# MCU_board_ATmega328p_v2_4_AW.net
KiCad netlist of a schematic drawn in EAGLE
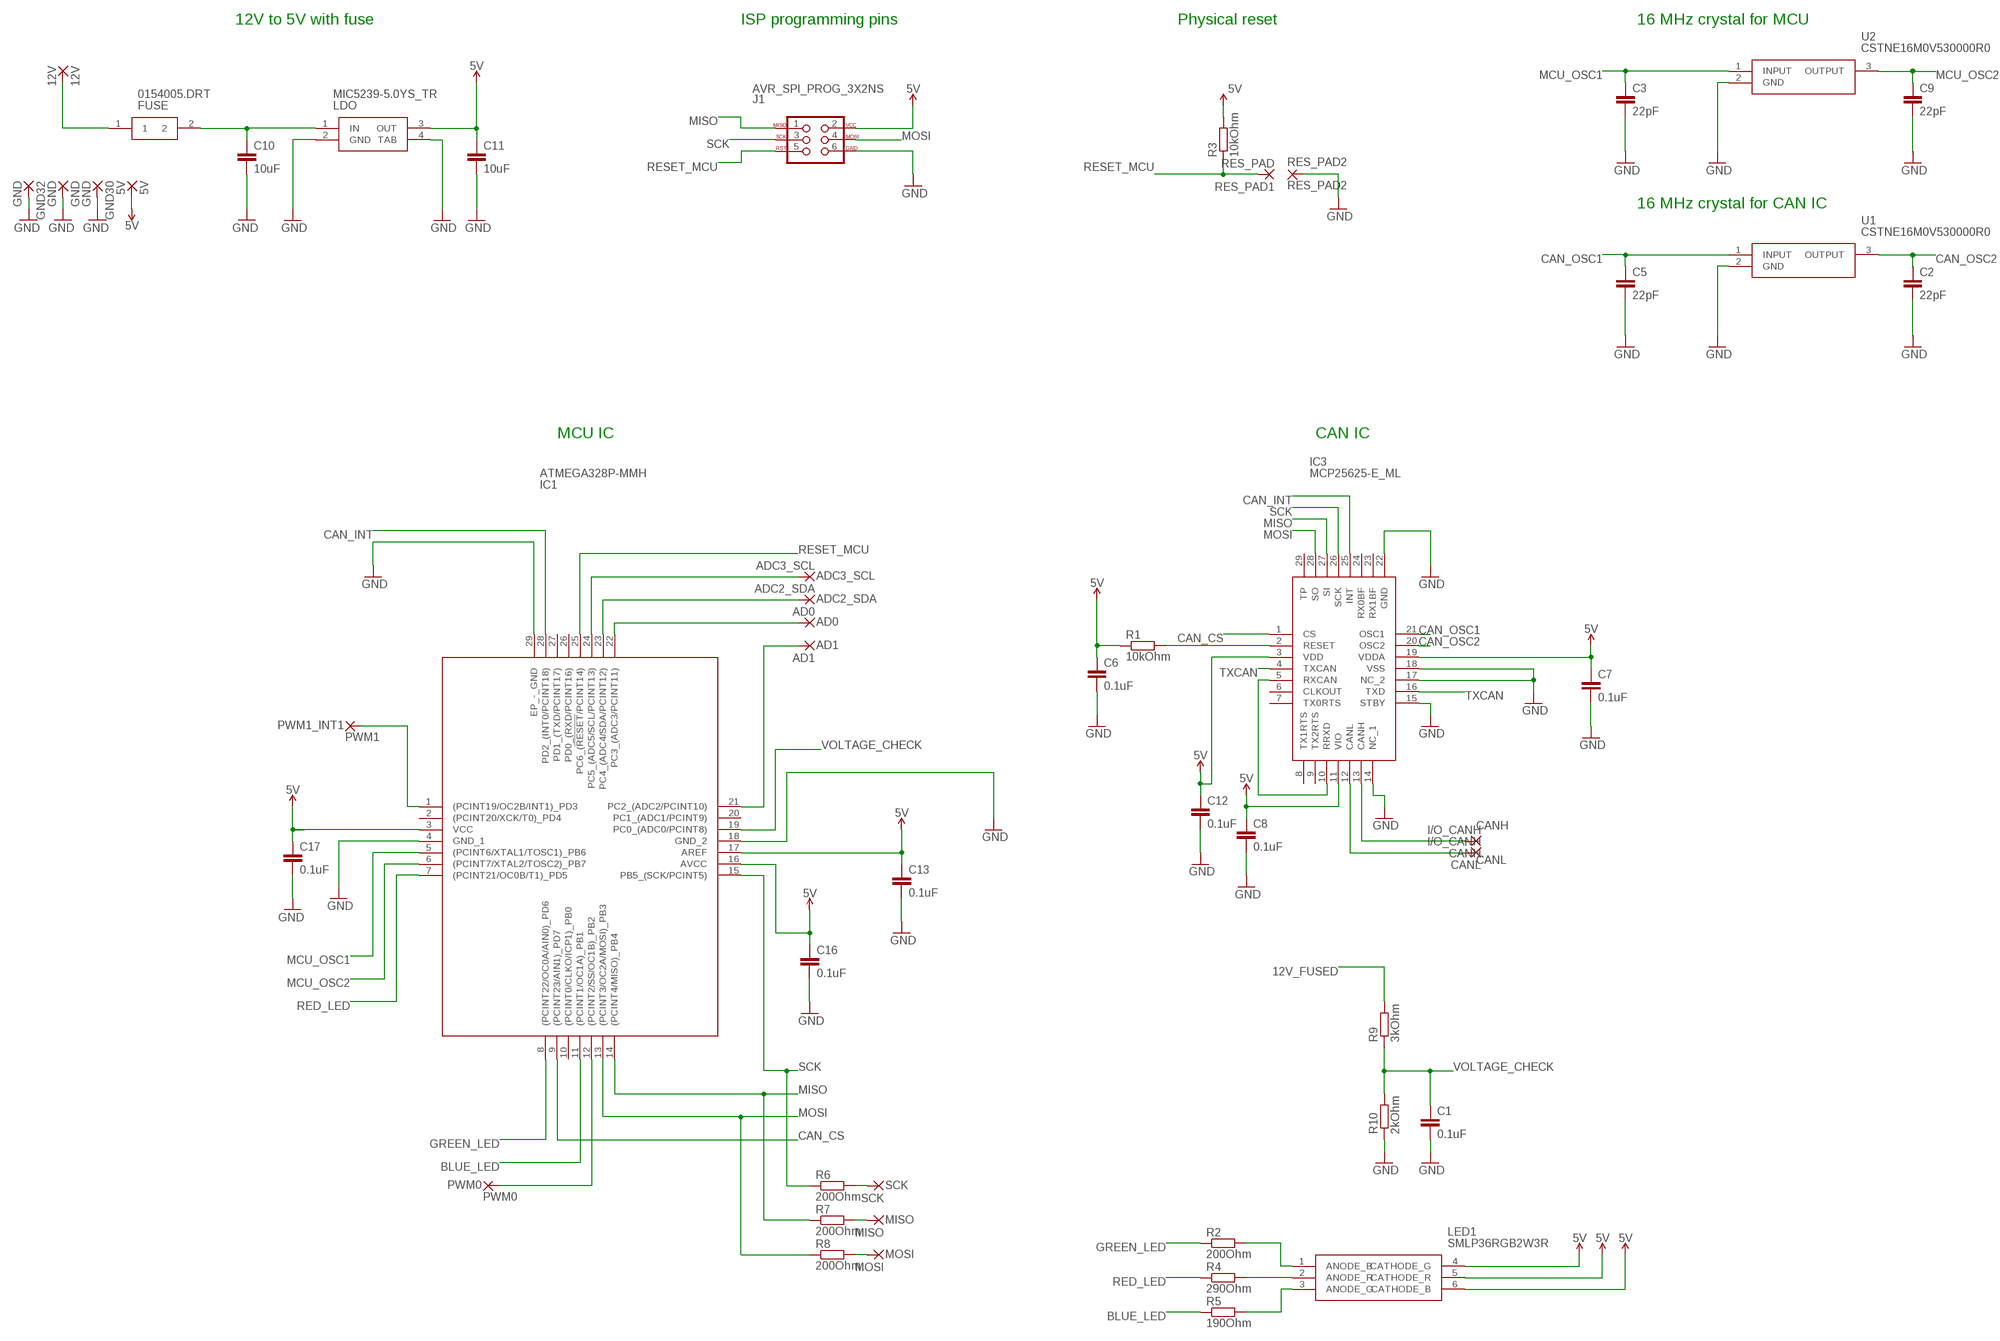
[diagram p0: schematic, sheet 1]

(export (version "E")
  (design (tool "Eeschema 10.0.6"))
  (components
    (comp (ref "5V")
      (value "5V")
      (footprint "eagle-import:2,15_1,0")
      (libsource (lib "eagle-import") (part "2,15/1,0"))
    )
    (comp (ref "12V")
      (value "12V")
      (footprint "eagle-import:2,15_1,0")
      (libsource (lib "eagle-import") (part "2,15/1,0"))
    )
    (comp (ref "AD0")
      (value "AD0")
      (footprint "eagle-import:2,15_1,0")
      (libsource (lib "eagle-import") (part "2,15/1,0"))
    )
    (comp (ref "AD1")
      (value "AD1")
      (footprint "eagle-import:2,15_1,0")
      (libsource (lib "eagle-import") (part "2,15/1,0"))
    )
    (comp (ref "ADC2_SDA")
      (value "ADC2_SDA")
      (footprint "eagle-import:2,15_1,0")
      (libsource (lib "eagle-import") (part "2,15/1,0"))
    )
    (comp (ref "ADC3_SCL")
      (value "ADC3_SCL")
      (footprint "eagle-import:2,15_1,0")
      (libsource (lib "eagle-import") (part "2,15/1,0"))
    )
    (comp (ref "C1")
      (value "0.1uF")
      (footprint "eagle-import:C0603")
      (libsource (lib "eagle-import") (part "CC0603"))
    )
    (comp (ref "C2")
      (value "22pF")
      (footprint "eagle-import:C0603")
      (libsource (lib "eagle-import") (part "CC0603"))
    )
    (comp (ref "C3")
      (value "22pF")
      (footprint "eagle-import:C0603")
      (libsource (lib "eagle-import") (part "CC0603"))
    )
    (comp (ref "C5")
      (value "22pF")
      (footprint "eagle-import:C0603")
      (libsource (lib "eagle-import") (part "CC0603"))
    )
    (comp (ref "C6")
      (value "0.1uF")
      (footprint "eagle-import:C0603")
      (libsource (lib "eagle-import") (part "CC0603"))
    )
    (comp (ref "C7")
      (value "0.1uF")
      (footprint "eagle-import:C0603")
      (libsource (lib "eagle-import") (part "CC0603"))
    )
    (comp (ref "C8")
      (value "0.1uF")
      (footprint "eagle-import:C0603")
      (libsource (lib "eagle-import") (part "CC0603"))
    )
    (comp (ref "C9")
      (value "22pF")
      (footprint "eagle-import:C0603")
      (libsource (lib "eagle-import") (part "CC0603"))
    )
    (comp (ref "C10")
      (value "10uF")
      (footprint "eagle-import:C0603")
      (libsource (lib "eagle-import") (part "CC0603"))
    )
    (comp (ref "C11")
      (value "10uF")
      (footprint "eagle-import:C0603")
      (libsource (lib "eagle-import") (part "CC0603"))
    )
    (comp (ref "C12")
      (value "0.1uF")
      (footprint "eagle-import:C0603")
      (libsource (lib "eagle-import") (part "CC0603"))
    )
    (comp (ref "C13")
      (value "0.1uF")
      (footprint "eagle-import:C0603")
      (libsource (lib "eagle-import") (part "CC0603"))
    )
    (comp (ref "C16")
      (value "0.1uF")
      (footprint "eagle-import:C0603")
      (libsource (lib "eagle-import") (part "CC0603"))
    )
    (comp (ref "C17")
      (value "0.1uF")
      (footprint "eagle-import:C0603")
      (libsource (lib "eagle-import") (part "CC0603"))
    )
    (comp (ref "CANH")
      (value "I/O_CANH")
      (footprint "eagle-import:2,15_1,0")
      (libsource (lib "eagle-import") (part "2,15/1,0"))
    )
    (comp (ref "CANL")
      (value "I/O_CANH")
      (footprint "eagle-import:2,15_1,0")
      (libsource (lib "eagle-import") (part "2,15/1,0"))
    )
    (comp (ref "FUSE")
      (value "0154005.DRT")
      (footprint "eagle-import:0154001.DRT")
      (fields (field (name "RS_PART_NUMBER") "2196260P"))
      (libsource (lib "eagle-import") (part "0154005.DRT"))
    )
    (comp (ref "GND")
      (value "GND")
      (footprint "eagle-import:2,15_1,0")
      (libsource (lib "eagle-import") (part "2,15/1,0"))
    )
    (comp (ref "GND30")
      (value "GND")
      (footprint "eagle-import:2,15_1,0")
      (libsource (lib "eagle-import") (part "2,15/1,0"))
    )
    (comp (ref "GND32")
      (value "GND")
      (footprint "eagle-import:2,15_1,0")
      (libsource (lib "eagle-import") (part "2,15/1,0"))
    )
    (comp (ref "IC1")
      (value "ATMEGA328P-MMH")
      (footprint "eagle-import:QFN45P400X400X100-29N")
      (fields (field (name "RS_PART_NUMBER") "1310272P"))
      (libsource (lib "eagle-import") (part "ATMEGA328P-MMH"))
    )
    (comp (ref "IC3")
      (value "MCP25625-E_ML")
      (footprint "eagle-import:QFN65P600X600X100-29N")
      (fields (field (name "ARROW_PART_NUMBER") "MCP25625-E/ML") (field (name "RS_PART_NUMBER") "1654104"))
      (libsource (lib "eagle-import") (part "MCP25625-E_ML"))
    )
    (comp (ref "J1")
      (value "AVR_SPI_PROG_3X2NS")
      (footprint "eagle-import:2X3-NS")
      (libsource (lib "eagle-import") (part "AVR_SPI_PROG_3X2NS"))
    )
    (comp (ref "LDO")
      (value "MIC5239-5.0YS_TR")
      (footprint "eagle-import:SOT230P700X170-4N")
      (fields
        (field (name "ARROW_PART_NUMBER") "MIC5239-5.0YS TR")
        (field (name "RS_PART_NUMBER") "7275535P")
      )
      (libsource (lib "eagle-import") (part "MIC5239-5.0YS_TR"))
    )
    (comp (ref "LED1")
      (value "SMLP36RGB2W3R")
      (footprint "eagle-import:ROHM-1510-(0604)")
      (fields (field (name "RS_PART_NUMBER") "1246884P"))
      (libsource (lib "eagle-import") (part "SMLP36RGB2W3R"))
    )
    (comp (ref "MISO")
      (value "MISO")
      (footprint "eagle-import:2,15_1,0")
      (libsource (lib "eagle-import") (part "2,15/1,0"))
    )
    (comp (ref "MOSI")
      (value "MOSI")
      (footprint "eagle-import:2,15_1,0")
      (libsource (lib "eagle-import") (part "2,15/1,0"))
    )
    (comp (ref "PWM0")
      (value "PWM0")
      (footprint "eagle-import:2,15_1,0")
      (libsource (lib "eagle-import") (part "2,15/1,0"))
    )
    (comp (ref "PWM1_INT1")
      (value "PWM1")
      (footprint "eagle-import:2,15_1,0")
      (libsource (lib "eagle-import") (part "2,15/1,0"))
    )
    (comp (ref "R1")
      (value "10kOhm")
      (footprint "eagle-import:R0603")
      (libsource (lib "eagle-import") (part "RR0603"))
    )
    (comp (ref "R2")
      (value "200Ohm")
      (footprint "eagle-import:R0603")
      (libsource (lib "eagle-import") (part "RR0603"))
    )
    (comp (ref "R3")
      (value "10kOhm")
      (footprint "eagle-import:R0603")
      (libsource (lib "eagle-import") (part "RR0603"))
    )
    (comp (ref "R4")
      (value "290Ohm")
      (footprint "eagle-import:R0603")
      (libsource (lib "eagle-import") (part "RR0603"))
    )
    (comp (ref "R5")
      (value "190Ohm")
      (footprint "eagle-import:R0603")
      (libsource (lib "eagle-import") (part "RR0603"))
    )
    (comp (ref "R6")
      (value "200Ohm")
      (footprint "eagle-import:R0603")
      (libsource (lib "eagle-import") (part "RR0603"))
    )
    (comp (ref "R7")
      (value "200Ohm")
      (footprint "eagle-import:R0603")
      (libsource (lib "eagle-import") (part "RR0603"))
    )
    (comp (ref "R8")
      (value "200Ohm")
      (footprint "eagle-import:R0603")
      (libsource (lib "eagle-import") (part "RR0603"))
    )
    (comp (ref "R9")
      (value "3kOhm")
      (footprint "eagle-import:R0603")
      (libsource (lib "eagle-import") (part "RR0603"))
    )
    (comp (ref "R10")
      (value "2kOhm")
      (footprint "eagle-import:R0603")
      (libsource (lib "eagle-import") (part "RR0603"))
    )
    (comp (ref "RES_PAD1")
      (value "RES_PAD")
      (footprint "eagle-import:SMD1,27-2,54")
      (libsource (lib "eagle-import") (part "SMD2"))
    )
    (comp (ref "RES_PAD2")
      (value "RES_PAD2")
      (footprint "eagle-import:SMD1,27-2,54")
      (libsource (lib "eagle-import") (part "SMD2"))
    )
    (comp (ref "SCK")
      (value "SCK")
      (footprint "eagle-import:2,15_1,0")
      (libsource (lib "eagle-import") (part "2,15/1,0"))
    )
    (comp (ref "U1")
      (value "CSTNE16M0V530000R0")
      (footprint "eagle-import:CSTNE16M0V530000R0")
      (libsource (lib "eagle-import") (part "CSTNE16M0V530000R0"))
    )
    (comp (ref "U2")
      (value "CSTNE16M0V530000R0")
      (footprint "eagle-import:CSTNE16M0V530000R0")
      (libsource (lib "eagle-import") (part "CSTNE16M0V530000R0"))
    )
  )
  (nets
    (net (code "1") (name "/12V_FUSED") (class "Default")
      (node (ref "C10") (pin "1") (pinfunction "1_1") (pintype "passive"))
      (node (ref "FUSE") (pin "2") (pinfunction "2_2") (pintype "bidirectional"))
      (node (ref "LDO") (pin "1") (pinfunction "IN_1") (pintype "bidirectional"))
      (node (ref "R9") (pin "2") (pinfunction "2_2") (pintype "passive"))
    )
    (net (code "2") (name "/BLUE_LED") (class "Default")
      (node (ref "IC1") (pin "11") (pinfunction "(PCINT1/OC1A)_PB1_11") (pintype "bidirectional"))
      (node (ref "R5") (pin "1") (pinfunction "1_1") (pintype "passive"))
    )
    (net (code "3") (name "/CANH") (class "Default")
      (node (ref "CANH") (pin "1") (pinfunction "P_1") (pintype "passive"))
      (node (ref "IC3") (pin "13") (pinfunction "CANH_13") (pintype "bidirectional"))
    )
    (net (code "4") (name "/CANL") (class "Default")
      (node (ref "CANL") (pin "1") (pinfunction "P_1") (pintype "passive"))
      (node (ref "IC3") (pin "12") (pinfunction "CANL_12") (pintype "bidirectional"))
    )
    (net (code "5") (name "/CAN_CS") (class "Default")
      (node (ref "IC1") (pin "9") (pinfunction "(PCINT23/AIN1)_PD7_9") (pintype "bidirectional"))
      (node (ref "IC3") (pin "1") (pinfunction "CS_1") (pintype "input"))
    )
    (net (code "6") (name "/CAN_INT") (class "Default")
      (node (ref "IC1") (pin "28") (pinfunction "PD2_(INT0/PCINT18)_28") (pintype "bidirectional"))
      (node (ref "IC3") (pin "25") (pinfunction "INT_25") (pintype "input"))
    )
    (net (code "7") (name "/CAN_OSC1") (class "Default")
      (node (ref "C5") (pin "1") (pinfunction "1_1") (pintype "passive"))
      (node (ref "IC3") (pin "21") (pinfunction "OSC1_21") (pintype "bidirectional"))
      (node (ref "U1") (pin "1") (pinfunction "INPUT_1") (pintype "bidirectional"))
    )
    (net (code "8") (name "/CAN_OSC2") (class "Default")
      (node (ref "C2") (pin "1") (pinfunction "1_1") (pintype "passive"))
      (node (ref "IC3") (pin "20") (pinfunction "OSC2_20") (pintype "bidirectional"))
      (node (ref "U1") (pin "3") (pinfunction "OUTPUT_3") (pintype "bidirectional"))
    )
    (net (code "9") (name "/GREEN_LED") (class "Default")
      (node (ref "IC1") (pin "8") (pinfunction "(PCINT22/OC0A/AIN0)_PD6_8") (pintype "bidirectional"))
      (node (ref "R2") (pin "1") (pinfunction "1_1") (pintype "passive"))
    )
    (net (code "10") (name "/MCU_OSC1") (class "Default")
      (node (ref "C3") (pin "1") (pinfunction "1_1") (pintype "passive"))
      (node (ref "IC1") (pin "5") (pinfunction "(PCINT6/XTAL1/TOSC1)_PB6_5") (pintype "bidirectional"))
      (node (ref "U2") (pin "1") (pinfunction "INPUT_1") (pintype "bidirectional"))
    )
    (net (code "11") (name "/MCU_OSC2") (class "Default")
      (node (ref "C9") (pin "1") (pinfunction "1_1") (pintype "passive"))
      (node (ref "IC1") (pin "6") (pinfunction "(PCINT7/XTAL2/TOSC2)_PB7_6") (pintype "bidirectional"))
      (node (ref "U2") (pin "3") (pinfunction "OUTPUT_3") (pintype "bidirectional"))
    )
    (net (code "12") (name "/MISO") (class "Default")
      (node (ref "IC1") (pin "14") (pinfunction "(PCINT4/MISO)_PB4_14") (pintype "bidirectional"))
      (node (ref "IC3") (pin "27") (pinfunction "SI_27") (pintype "bidirectional"))
      (node (ref "J1") (pin "1") (pinfunction "1_1") (pintype "passive"))
      (node (ref "R7") (pin "1") (pinfunction "1_1") (pintype "passive"))
    )
    (net (code "13") (name "/MOSI") (class "Default")
      (node (ref "IC1") (pin "13") (pinfunction "(PCINT3/OC2A/MOSI)_PB3_13") (pintype "bidirectional"))
      (node (ref "IC3") (pin "28") (pinfunction "SO_28") (pintype "bidirectional"))
      (node (ref "J1") (pin "4") (pinfunction "4_4") (pintype "passive"))
      (node (ref "R8") (pin "1") (pinfunction "1_1") (pintype "passive"))
    )
    (net (code "14") (name "/RED_LED") (class "Default")
      (node (ref "IC1") (pin "7") (pinfunction "(PCINT21/OC0B/T1)_PD5_7") (pintype "bidirectional"))
      (node (ref "R4") (pin "1") (pinfunction "1_1") (pintype "passive"))
    )
    (net (code "15") (name "/RESET_MCU") (class "Default")
      (node (ref "IC1") (pin "25") (pinfunction "PC6_(~{RESET}/PCINT14)_25") (pintype "bidirectional"))
      (node (ref "J1") (pin "5") (pinfunction "5_5") (pintype "passive"))
      (node (ref "R3") (pin "1") (pinfunction "1_1") (pintype "passive"))
      (node (ref "RES_PAD1") (pin "1") (pinfunction "P_1") (pintype "passive"))
    )
    (net (code "16") (name "/SCK") (class "Default")
      (node (ref "IC1") (pin "15") (pinfunction "PB5_(SCK/PCINT5)_15") (pintype "bidirectional"))
      (node (ref "IC3") (pin "26") (pinfunction "SCK_26") (pintype "bidirectional"))
      (node (ref "J1") (pin "3") (pinfunction "3_3") (pintype "passive"))
      (node (ref "R6") (pin "1") (pinfunction "1_1") (pintype "passive"))
    )
    (net (code "17") (name "/TXCAN") (class "Default")
      (node (ref "IC3") (pin "16") (pinfunction "TXD_16") (pintype "bidirectional"))
      (node (ref "IC3") (pin "4") (pinfunction "TXCAN_4") (pintype "bidirectional"))
    )
    (net (code "18") (name "/VOLTAGE_CHECK") (class "Default")
      (node (ref "C1") (pin "1") (pinfunction "1_1") (pintype "passive"))
      (node (ref "IC1") (pin "19") (pinfunction "PC0_(ADC0/PCINT8)_19") (pintype "bidirectional"))
      (node (ref "R10") (pin "2") (pinfunction "2_2") (pintype "passive"))
      (node (ref "R9") (pin "1") (pinfunction "1_1") (pintype "passive"))
    )
    (net (code "19") (name "5V") (class "Default")
      (node (ref "5V") (pin "1") (pinfunction "P_1") (pintype "passive"))
      (node (ref "C11") (pin "1") (pinfunction "1_1") (pintype "passive"))
      (node (ref "C12") (pin "1") (pinfunction "1_1") (pintype "passive"))
      (node (ref "C13") (pin "1") (pinfunction "1_1") (pintype "passive"))
      (node (ref "C16") (pin "1") (pinfunction "1_1") (pintype "passive"))
      (node (ref "C17") (pin "1") (pinfunction "1_1") (pintype "passive"))
      (node (ref "C6") (pin "1") (pinfunction "1_1") (pintype "passive"))
      (node (ref "C7") (pin "1") (pinfunction "1_1") (pintype "passive"))
      (node (ref "C8") (pin "1") (pinfunction "1_1") (pintype "passive"))
      (node (ref "IC1") (pin "16") (pinfunction "AVCC_16") (pintype "bidirectional"))
      (node (ref "IC1") (pin "17") (pinfunction "AREF_17") (pintype "bidirectional"))
      (node (ref "IC1") (pin "3") (pinfunction "VCC_3") (pintype "bidirectional"))
      (node (ref "IC3") (pin "11") (pinfunction "VIO_11") (pintype "bidirectional"))
      (node (ref "IC3") (pin "19") (pinfunction "VDDA_19") (pintype "power_in"))
      (node (ref "IC3") (pin "3") (pinfunction "VDD_3") (pintype "power_in"))
      (node (ref "J1") (pin "2") (pinfunction "2_2") (pintype "passive"))
      (node (ref "LDO") (pin "3") (pinfunction "OUT_3") (pintype "bidirectional"))
      (node (ref "LED1") (pin "4") (pinfunction "CATHODE_G_4") (pintype "bidirectional"))
      (node (ref "LED1") (pin "5") (pinfunction "CATHODE_R_5") (pintype "bidirectional"))
      (node (ref "LED1") (pin "6") (pinfunction "CATHODE_B_6") (pintype "bidirectional"))
      (node (ref "R1") (pin "1") (pinfunction "1_1") (pintype "passive"))
      (node (ref "R3") (pin "2") (pinfunction "2_2") (pintype "passive"))
    )
    (net (code "20") (name "GND") (class "Default")
      (node (ref "C1") (pin "2") (pinfunction "2_2") (pintype "passive"))
      (node (ref "C10") (pin "2") (pinfunction "2_2") (pintype "passive"))
      (node (ref "C11") (pin "2") (pinfunction "2_2") (pintype "passive"))
      (node (ref "C12") (pin "2") (pinfunction "2_2") (pintype "passive"))
      (node (ref "C13") (pin "2") (pinfunction "2_2") (pintype "passive"))
      (node (ref "C16") (pin "2") (pinfunction "2_2") (pintype "passive"))
      (node (ref "C17") (pin "2") (pinfunction "2_2") (pintype "passive"))
      (node (ref "C2") (pin "2") (pinfunction "2_2") (pintype "passive"))
      (node (ref "C3") (pin "2") (pinfunction "2_2") (pintype "passive"))
      (node (ref "C5") (pin "2") (pinfunction "2_2") (pintype "passive"))
      (node (ref "C6") (pin "2") (pinfunction "2_2") (pintype "passive"))
      (node (ref "C7") (pin "2") (pinfunction "2_2") (pintype "passive"))
      (node (ref "C8") (pin "2") (pinfunction "2_2") (pintype "passive"))
      (node (ref "C9") (pin "2") (pinfunction "2_2") (pintype "passive"))
      (node (ref "GND") (pin "1") (pinfunction "P_1") (pintype "passive"))
      (node (ref "GND30") (pin "1") (pinfunction "P_1") (pintype "passive"))
      (node (ref "GND32") (pin "1") (pinfunction "P_1") (pintype "passive"))
      (node (ref "IC1") (pin "18") (pinfunction "GND_2_18") (pintype "bidirectional"))
      (node (ref "IC1") (pin "29") (pinfunction "EP_-_GND_29") (pintype "bidirectional"))
      (node (ref "IC1") (pin "4") (pinfunction "GND_1_4") (pintype "bidirectional"))
      (node (ref "IC3") (pin "14") (pinfunction "NC_1_14") (pintype "bidirectional"))
      (node (ref "IC3") (pin "15") (pinfunction "STBY_15") (pintype "bidirectional"))
      (node (ref "IC3") (pin "17") (pinfunction "NC_2_17") (pintype "bidirectional"))
      (node (ref "IC3") (pin "18") (pinfunction "VSS_18") (pintype "power_in"))
      (node (ref "IC3") (pin "22") (pinfunction "GND_22") (pintype "power_in"))
      (node (ref "J1") (pin "6") (pinfunction "6_6") (pintype "passive"))
      (node (ref "LDO") (pin "2") (pinfunction "GND_2") (pintype "bidirectional"))
      (node (ref "LDO") (pin "4") (pinfunction "TAB_4") (pintype "bidirectional"))
      (node (ref "R10") (pin "1") (pinfunction "1_1") (pintype "passive"))
      (node (ref "RES_PAD2") (pin "1") (pinfunction "P_1") (pintype "passive"))
      (node (ref "U1") (pin "2") (pinfunction "GND_2") (pintype "bidirectional"))
      (node (ref "U2") (pin "2") (pinfunction "GND_2") (pintype "bidirectional"))
    )
    (net (code "21") (name "Net-(12V-P)") (class "Default")
      (node (ref "12V") (pin "1") (pinfunction "P_1") (pintype "passive"))
      (node (ref "FUSE") (pin "1") (pinfunction "1_1") (pintype "bidirectional"))
    )
    (net (code "22") (name "Net-(AD0-P)") (class "Default")
      (node (ref "AD0") (pin "1") (pinfunction "P_1") (pintype "passive"))
      (node (ref "IC1") (pin "22") (pinfunction "PC3_(ADC3/PCINT11)_22") (pintype "bidirectional"))
    )
    (net (code "23") (name "Net-(AD1-P)") (class "Default")
      (node (ref "AD1") (pin "1") (pinfunction "P_1") (pintype "passive"))
      (node (ref "IC1") (pin "21") (pinfunction "PC2_(ADC2/PCINT10)_21") (pintype "bidirectional"))
    )
    (net (code "24") (name "Net-(ADC2_SDA-P)") (class "Default")
      (node (ref "ADC2_SDA") (pin "1") (pinfunction "P_1") (pintype "passive"))
      (node (ref "IC1") (pin "23") (pinfunction "PC4_(ADC4/SDA/PCINT12)_23") (pintype "bidirectional"))
    )
    (net (code "25") (name "Net-(ADC3_SCL-P)") (class "Default")
      (node (ref "ADC3_SCL") (pin "1") (pinfunction "P_1") (pintype "passive"))
      (node (ref "IC1") (pin "24") (pinfunction "PC5_(ADC5/SCL/PCINT13)_24") (pintype "bidirectional"))
    )
    (net (code "26") (name "Net-(IC1-(PCINT2{slash}SS{slash}OC1B)_PB2)") (class "Default")
      (node (ref "IC1") (pin "12") (pinfunction "(PCINT2/SS/OC1B)_PB2_12") (pintype "bidirectional"))
      (node (ref "PWM0") (pin "1") (pinfunction "P_1") (pintype "passive"))
    )
    (net (code "27") (name "Net-(IC1-(PCINT19{slash}OC2B{slash}INT1)_PD3)") (class "Default")
      (node (ref "IC1") (pin "1") (pinfunction "(PCINT19/OC2B/INT1)_PD3_1") (pintype "bidirectional"))
      (node (ref "PWM1_INT1") (pin "1") (pinfunction "P_1") (pintype "passive"))
    )
    (net (code "28") (name "Net-(IC3-RESET)") (class "Default")
      (node (ref "IC3") (pin "2") (pinfunction "RESET_2") (pintype "bidirectional"))
      (node (ref "R1") (pin "2") (pinfunction "2_2") (pintype "passive"))
    )
    (net (code "29") (name "Net-(IC3-RRXD)") (class "Default")
      (node (ref "IC3") (pin "10") (pinfunction "RRXD_10") (pintype "bidirectional"))
      (node (ref "IC3") (pin "5") (pinfunction "RXCAN_5") (pintype "bidirectional"))
    )
    (net (code "30") (name "Net-(LED1-ANODE_B)") (class "Default")
      (node (ref "LED1") (pin "1") (pinfunction "ANODE_B_1") (pintype "bidirectional"))
      (node (ref "R2") (pin "2") (pinfunction "2_2") (pintype "passive"))
    )
    (net (code "31") (name "Net-(LED1-ANODE_G)") (class "Default")
      (node (ref "LED1") (pin "3") (pinfunction "ANODE_G_3") (pintype "bidirectional"))
      (node (ref "R5") (pin "2") (pinfunction "2_2") (pintype "passive"))
    )
    (net (code "32") (name "Net-(LED1-ANODE_R)") (class "Default")
      (node (ref "LED1") (pin "2") (pinfunction "ANODE_R_2") (pintype "bidirectional"))
      (node (ref "R4") (pin "2") (pinfunction "2_2") (pintype "passive"))
    )
    (net (code "33") (name "Net-(MISO-P)") (class "Default")
      (node (ref "MISO") (pin "1") (pinfunction "P_1") (pintype "passive"))
      (node (ref "R7") (pin "2") (pinfunction "2_2") (pintype "passive"))
    )
    (net (code "34") (name "Net-(MOSI-P)") (class "Default")
      (node (ref "MOSI") (pin "1") (pinfunction "P_1") (pintype "passive"))
      (node (ref "R8") (pin "2") (pinfunction "2_2") (pintype "passive"))
    )
    (net (code "35") (name "Net-(SCK-P)") (class "Default")
      (node (ref "R6") (pin "2") (pinfunction "2_2") (pintype "passive"))
      (node (ref "SCK") (pin "1") (pinfunction "P_1") (pintype "passive"))
    )
    (net (code "36") (name "unconnected-(IC1-(PCINT0{slash}CLKO{slash}ICP1)_PB0-Pad10)") (class "Default")
      (node (ref "IC1") (pin "10") (pinfunction "(PCINT0/CLKO/ICP1)_PB0_10") (pintype "bidirectional"))
    )
    (net (code "37") (name "unconnected-(IC1-(PCINT20{slash}XCK{slash}T0)_PD4-Pad2)") (class "Default")
      (node (ref "IC1") (pin "2") (pinfunction "(PCINT20/XCK/T0)_PD4_2") (pintype "bidirectional"))
    )
    (net (code "38") (name "unconnected-(IC1-PC1_(ADC1{slash}PCINT9)-Pad20)") (class "Default")
      (node (ref "IC1") (pin "20") (pinfunction "PC1_(ADC1/PCINT9)_20") (pintype "bidirectional"))
    )
    (net (code "39") (name "unconnected-(IC1-PD0_(RXD{slash}PCINT16)-Pad26)") (class "Default")
      (node (ref "IC1") (pin "26") (pinfunction "PD0_(RXD/PCINT16)_26") (pintype "bidirectional"))
    )
    (net (code "40") (name "unconnected-(IC1-PD1_(TXD{slash}PCINT17)-Pad27)") (class "Default")
      (node (ref "IC1") (pin "27") (pinfunction "PD1_(TXD/PCINT17)_27") (pintype "bidirectional"))
    )
    (net (code "41") (name "unconnected-(IC3-CLKOUT-Pad6)") (class "Default")
      (node (ref "IC3") (pin "6") (pinfunction "CLKOUT_6") (pintype "output"))
    )
    (net (code "42") (name "unconnected-(IC3-RX0BF-Pad24)") (class "Default")
      (node (ref "IC3") (pin "24") (pinfunction "RX0BF_24") (pintype "bidirectional"))
    )
    (net (code "43") (name "unconnected-(IC3-RX1BF-Pad23)") (class "Default")
      (node (ref "IC3") (pin "23") (pinfunction "RX1BF_23") (pintype "bidirectional"))
    )
    (net (code "44") (name "unconnected-(IC3-TP-Pad29)") (class "Default")
      (node (ref "IC3") (pin "29") (pinfunction "TP_29") (pintype "bidirectional"))
    )
    (net (code "45") (name "unconnected-(IC3-TX0RTS-Pad7)") (class "Default")
      (node (ref "IC3") (pin "7") (pinfunction "TX0RTS_7") (pintype "bidirectional"))
    )
    (net (code "46") (name "unconnected-(IC3-TX1RTS-Pad8)") (class "Default")
      (node (ref "IC3") (pin "8") (pinfunction "TX1RTS_8") (pintype "bidirectional"))
    )
    (net (code "47") (name "unconnected-(IC3-TX2RTS-Pad9)") (class "Default")
      (node (ref "IC3") (pin "9") (pinfunction "TX2RTS_9") (pintype "bidirectional"))
    )
  )
)
